# face_board.net
KiCad netlist of a schematic drawn in Altium Designer
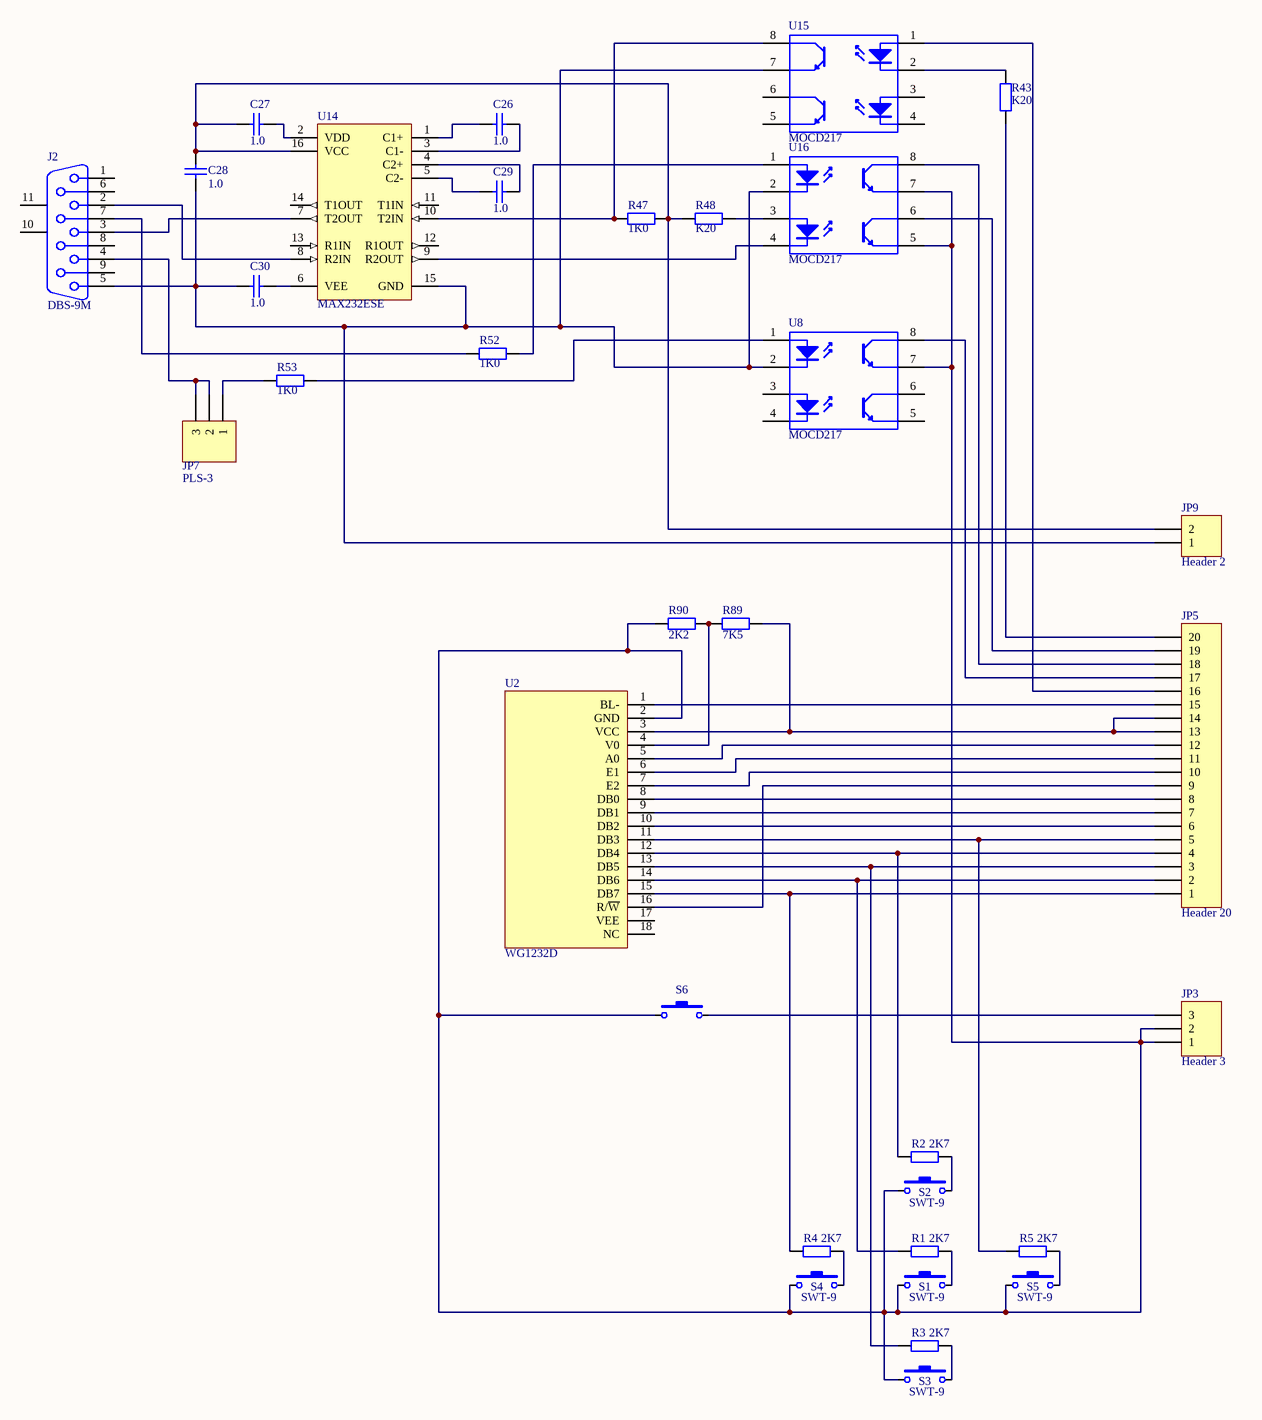
[diagram p0: face_board.SchDoc]

(export (version "E")
  (design (tool "Eeschema 10.0.6"))
  (components
    (comp (ref "C26")
      (value "1.0")
      (footprint "C3216-1206")
      (description "Capacitor (Semiconductor SIM Model)")
      (fields (field (name "MANUFACTURER") "Generic Components") (field (name "PUBLISHER") "Altium Limited"))
      (libsource (lib "Miscellaneous Devices") (part "Cap Semi"))
    )
    (comp (ref "C27")
      (value "1.0")
      (footprint "_1206")
      (description "Capacitor (Semiconductor SIM Model)")
      (fields (field (name "MANUFACTURER") "Generic Components") (field (name "PUBLISHER") "Altium Limited"))
      (libsource (lib "Miscellaneous Devices") (part "Cap Semi"))
    )
    (comp (ref "C28")
      (value "1.0")
      (footprint "C3216-1206")
      (description "Capacitor (Semiconductor SIM Model)")
      (fields (field (name "MANUFACTURER") "Generic Components") (field (name "PUBLISHER") "Altium Limited"))
      (libsource (lib "") (part "Cap Semi_1"))
    )
    (comp (ref "C29")
      (value "1.0")
      (footprint "C3216-1206")
      (description "Capacitor (Semiconductor SIM Model)")
      (fields (field (name "MANUFACTURER") "Generic Components") (field (name "PUBLISHER") "Altium Limited"))
      (libsource (lib "Miscellaneous Devices") (part "Cap Semi"))
    )
    (comp (ref "C30")
      (value "1.0")
      (footprint "C3216-1206")
      (description "Capacitor (Semiconductor SIM Model)")
      (fields (field (name "MANUFACTURER") "Generic Components") (field (name "PUBLISHER") "Altium Limited"))
      (libsource (lib "Miscellaneous Devices") (part "Cap Semi"))
    )
    (comp (ref "J2")
      (value "DBS-9M")
      (footprint "DSUB_N9")
      (description "Receptacle Assembly, 9 Position, Right Angle")
      (fields (field (name "MANUFACTURER") "Generic Components") (field (name "PUBLISHER") "Altium Limited"))
      (libsource (lib "Miscellaneous Connectors") (part "D Connector 9"))
    )
    (comp (ref "JP3")
      (value "Header 3")
      (footprint "HDR1X3")
      (description "Header, 3-Pin")
      (fields (field (name "MANUFACTURER") "Generic Components") (field (name "PUBLISHER") "Altium Limited"))
      (libsource (lib "") (part "Header 3_1"))
    )
    (comp (ref "JP5")
      (value "Header 20")
      (footprint "HDR1X20")
      (description "Header, 20-Pin")
      (fields (field (name "MANUFACTURER") "Generic Components") (field (name "PUBLISHER") "Altium Limited"))
      (libsource (lib "Miscellaneous Connectors") (part "Header 20"))
    )
    (comp (ref "JP7")
      (value "PLS-3")
      (footprint "HDR1X3")
      (description "Header, 3-Pin")
      (fields (field (name "MANUFACTURER") "Generic Components") (field (name "PUBLISHER") "Altium Limited"))
      (libsource (lib "Miscellaneous Connectors") (part "Header 3"))
    )
    (comp (ref "JP9")
      (value "Header 2")
      (footprint "HDR1X2")
      (description "Header, 2-Pin")
      (fields (field (name "MANUFACTURER") "Generic Components") (field (name "PUBLISHER") "Altium Limited"))
      (libsource (lib "Miscellaneous Connectors") (part "Header 2"))
    )
    (comp (ref "R1")
      (value "2K7")
      (footprint "_1206")
      (description "Resistor")
      (fields (field (name "MANUFACTURER") "Generic Components") (field (name "PUBLISHER") "Altium Limited"))
      (libsource (lib "Miscellaneous Devices") (part "Res2"))
    )
    (comp (ref "R2")
      (value "2K7")
      (footprint "_1206")
      (description "Resistor")
      (fields (field (name "MANUFACTURER") "Generic Components") (field (name "PUBLISHER") "Altium Limited"))
      (libsource (lib "Miscellaneous Devices") (part "Res2"))
    )
    (comp (ref "R3")
      (value "2K7")
      (footprint "_1206")
      (description "Resistor")
      (fields (field (name "MANUFACTURER") "Generic Components") (field (name "PUBLISHER") "Altium Limited"))
      (libsource (lib "Miscellaneous Devices") (part "Res2"))
    )
    (comp (ref "R4")
      (value "2K7")
      (footprint "_1206")
      (description "Resistor")
      (fields (field (name "MANUFACTURER") "Generic Components") (field (name "PUBLISHER") "Altium Limited"))
      (libsource (lib "Miscellaneous Devices") (part "Res2"))
    )
    (comp (ref "R5")
      (value "2K7")
      (footprint "_1206")
      (description "Resistor")
      (fields (field (name "MANUFACTURER") "Generic Components") (field (name "PUBLISHER") "Altium Limited"))
      (libsource (lib "Miscellaneous Devices") (part "Res2"))
    )
    (comp (ref "R43")
      (value "K20")
      (footprint "_1206")
      (description "Resistor")
      (fields (field (name "MANUFACTURER") "Generic Components") (field (name "PUBLISHER") "Altium Limited"))
      (libsource (lib "") (part "Res2_2"))
    )
    (comp (ref "R47")
      (value "1K0")
      (footprint "_1206")
      (description "Resistor")
      (fields (field (name "MANUFACTURER") "Generic Components") (field (name "PUBLISHER") "Altium Limited"))
      (libsource (lib "Miscellaneous Devices") (part "Res2"))
    )
    (comp (ref "R48")
      (value "K20")
      (footprint "_1206")
      (description "Resistor")
      (fields (field (name "MANUFACTURER") "Generic Components") (field (name "PUBLISHER") "Altium Limited"))
      (libsource (lib "Miscellaneous Devices") (part "Res2"))
    )
    (comp (ref "R52")
      (value "1K0")
      (footprint "_1206")
      (description "Resistor")
      (fields (field (name "MANUFACTURER") "Generic Components") (field (name "PUBLISHER") "Altium Limited"))
      (libsource (lib "Miscellaneous Devices") (part "Res2"))
    )
    (comp (ref "R53")
      (value "1K0")
      (footprint "_1206")
      (description "Resistor")
      (fields (field (name "MANUFACTURER") "Generic Components") (field (name "PUBLISHER") "Altium Limited"))
      (libsource (lib "Miscellaneous Devices") (part "Res2"))
    )
    (comp (ref "R89")
      (value "7K5")
      (footprint "_1206")
      (description "Resistor")
      (fields (field (name "MANUFACTURER") "Generic Components") (field (name "PUBLISHER") "Altium Limited"))
      (libsource (lib "") (part "Res2_1"))
    )
    (comp (ref "R90")
      (value "2K2")
      (footprint "_1206")
      (description "Resistor")
      (fields (field (name "MANUFACTURER") "Generic Components") (field (name "PUBLISHER") "Altium Limited"))
      (libsource (lib "") (part "Res2_1"))
    )
    (comp (ref "S1")
      (value "SWT-9")
      (footprint "SWT-9")
      (description "Switch")
      (fields (field (name "MANUFACTURER") "Generic Components") (field (name "PUBLISHER") "Altium Limited"))
      (libsource (lib "PAL") (part "SWT-9"))
    )
    (comp (ref "S2")
      (value "SWT-9")
      (footprint "SWT-9")
      (description "Switch")
      (fields (field (name "MANUFACTURER") "Generic Components") (field (name "PUBLISHER") "Altium Limited"))
      (libsource (lib "PAL") (part "SWT-9"))
    )
    (comp (ref "S3")
      (value "SWT-9")
      (footprint "SWT-9")
      (description "Switch")
      (fields (field (name "MANUFACTURER") "Generic Components") (field (name "PUBLISHER") "Altium Limited"))
      (libsource (lib "PAL") (part "SWT-9"))
    )
    (comp (ref "S4")
      (value "SWT-9")
      (footprint "SWT-9")
      (description "Switch")
      (fields (field (name "MANUFACTURER") "Generic Components") (field (name "PUBLISHER") "Altium Limited"))
      (libsource (lib "PAL") (part "SWT-9"))
    )
    (comp (ref "S5")
      (value "SWT-9")
      (footprint "SWT-9")
      (description "Switch")
      (fields (field (name "MANUFACTURER") "Generic Components") (field (name "PUBLISHER") "Altium Limited"))
      (libsource (lib "PAL") (part "SWT-9"))
    )
    (comp (ref "S6")
      (value "SWT-6")
      (footprint "SWT-6")
      (description "Button")
      (fields (field (name "MANUFACTURER") "Generic Components") (field (name "PUBLISHER") "Altium Limited"))
      (libsource (lib "PAL") (part "SWT-9"))
    )
    (comp (ref "U2") (value "WG1232D") (footprint "WG1232D") (libsource (lib "PAL") (part "WG1232D")))
    (comp (ref "U8") (value "MOCD217") (footprint "SO-G8") (libsource (lib "PAL") (part "MOCD217")))
    (comp (ref "U14")
      (value "MAX232ESE")
      (footprint "SO-G16")
      (description "+5V Powered, Multi-Channel RS-232 Driver/Receiver")
      (fields (field (name "MANUFACTURER") "Maxim") (field (name "PUBLISHER") "Altium Limited"))
      (libsource (lib "Maxim Communication Transceiver") (part "MAX232ESE"))
    )
    (comp (ref "U15") (value "MOCD217") (footprint "SO-G8") (libsource (lib "PAL") (part "MOCD217")))
    (comp (ref "U16") (value "MOCD217") (footprint "SO-G8") (libsource (lib "PAL") (part "MOCD217")))
  )
  (nets
    (net (code "1") (name "Net-(J2-Pad4)") (class "Default")
      (node (ref "J2") (pin "4") (pinfunction "4_4") (pintype "passive"))
      (node (ref "JP7") (pin "2") (pinfunction "2_2") (pintype "passive"))
      (node (ref "JP7") (pin "3") (pinfunction "3_3") (pintype "passive"))
    )
    (net (code "2") (name "Net-(J2-Pad7)") (class "Default")
      (node (ref "J2") (pin "7") (pinfunction "7_7") (pintype "passive"))
      (node (ref "R52") (pin "2") (pinfunction "2_2") (pintype "passive"))
    )
    (net (code "3") (name "Net-(JP3-Pad3)") (class "Default")
      (node (ref "JP3") (pin "3") (pinfunction "3_3") (pintype "passive"))
      (node (ref "S6") (pin "2") (pinfunction "2_2") (pintype "passive"))
    )
    (net (code "4") (name "Net-(JP5-Pad16)") (class "Default")
      (node (ref "JP5") (pin "16") (pinfunction "16_16") (pintype "passive"))
      (node (ref "U15") (pin "1") (pinfunction "A_1") (pintype "passive"))
    )
    (net (code "5") (name "Net-(JP5-Pad17)") (class "Default")
      (node (ref "JP5") (pin "17") (pinfunction "17_17") (pintype "passive"))
      (node (ref "U8") (pin "8") (pinfunction "C_8") (pintype "passive"))
    )
    (net (code "6") (name "Net-(JP5-Pad18)") (class "Default")
      (node (ref "JP5") (pin "18") (pinfunction "18_18") (pintype "passive"))
      (node (ref "U16") (pin "8") (pinfunction "C_8") (pintype "passive"))
    )
    (net (code "7") (name "Net-(JP5-Pad19)") (class "Default")
      (node (ref "JP5") (pin "19") (pinfunction "19_19") (pintype "passive"))
      (node (ref "U16") (pin "6") (pinfunction "C_6") (pintype "passive"))
    )
    (net (code "8") (name "Net-(JP5-Pad20)") (class "Default")
      (node (ref "JP5") (pin "20") (pinfunction "20_20") (pintype "passive"))
      (node (ref "R43") (pin "1") (pinfunction "1_1") (pintype "passive"))
    )
    (net (code "9") (name "Net-(JP7-Pad1)") (class "Default")
      (node (ref "JP7") (pin "1") (pinfunction "1_1") (pintype "passive"))
      (node (ref "R53") (pin "2") (pinfunction "2_2") (pintype "passive"))
    )
    (net (code "10") (name "Net-(R1-Pad1)") (class "Default")
      (node (ref "R1") (pin "1") (pinfunction "1_1") (pintype "passive"))
      (node (ref "S1") (pin "2") (pinfunction "2_2") (pintype "passive"))
    )
    (net (code "11") (name "Net-(R2-Pad1)") (class "Default")
      (node (ref "R2") (pin "1") (pinfunction "1_1") (pintype "passive"))
      (node (ref "S2") (pin "2") (pinfunction "2_2") (pintype "passive"))
    )
    (net (code "12") (name "Net-(R3-Pad1)") (class "Default")
      (node (ref "R3") (pin "1") (pinfunction "1_1") (pintype "passive"))
      (node (ref "S3") (pin "2") (pinfunction "2_2") (pintype "passive"))
    )
    (net (code "13") (name "Net-(R4-Pad1)") (class "Default")
      (node (ref "R4") (pin "1") (pinfunction "1_1") (pintype "passive"))
      (node (ref "S4") (pin "2") (pinfunction "2_2") (pintype "passive"))
    )
    (net (code "14") (name "Net-(R5-Pad1)") (class "Default")
      (node (ref "R5") (pin "1") (pinfunction "1_1") (pintype "passive"))
      (node (ref "S5") (pin "2") (pinfunction "2_2") (pintype "passive"))
    )
    (net (code "15") (name "Net-(R43-Pad2)") (class "Default")
      (node (ref "R43") (pin "2") (pinfunction "2_2") (pintype "passive"))
      (node (ref "U15") (pin "2") (pinfunction "K_2") (pintype "passive"))
    )
    (net (code "16") (name "Net-(R48-Pad1)") (class "Default")
      (node (ref "R48") (pin "1") (pinfunction "1_1") (pintype "passive"))
      (node (ref "U16") (pin "3") (pinfunction "A_3") (pintype "passive"))
    )
    (net (code "17") (name "Net-(R52-Pad1)") (class "Default")
      (node (ref "R52") (pin "1") (pinfunction "1_1") (pintype "passive"))
      (node (ref "U16") (pin "1") (pinfunction "A_1") (pintype "passive"))
    )
    (net (code "18") (name "Net-(R53-Pad1)") (class "Default")
      (node (ref "R53") (pin "1") (pinfunction "1_1") (pintype "passive"))
      (node (ref "U8") (pin "1") (pinfunction "A_1") (pintype "passive"))
    )
    (net (code "19") (name "Net-(U2-A0)") (class "Default")
      (node (ref "JP5") (pin "12") (pinfunction "12_12") (pintype "passive"))
      (node (ref "U2") (pin "5") (pinfunction "A0_5") (pintype "passive"))
    )
    (net (code "20") (name "Net-(U2-BL-)") (class "Default")
      (node (ref "JP5") (pin "15") (pinfunction "15_15") (pintype "passive"))
      (node (ref "U2") (pin "1") (pinfunction "BL-_1") (pintype "passive"))
    )
    (net (code "21") (name "Net-(U2-DB0)") (class "Default")
      (node (ref "JP5") (pin "8") (pinfunction "8_8") (pintype "passive"))
      (node (ref "U2") (pin "8") (pinfunction "DB0_8") (pintype "passive"))
    )
    (net (code "22") (name "Net-(U2-DB1)") (class "Default")
      (node (ref "JP5") (pin "7") (pinfunction "7_7") (pintype "passive"))
      (node (ref "U2") (pin "9") (pinfunction "DB1_9") (pintype "passive"))
    )
    (net (code "23") (name "Net-(U2-DB2)") (class "Default")
      (node (ref "JP5") (pin "6") (pinfunction "6_6") (pintype "passive"))
      (node (ref "U2") (pin "10") (pinfunction "DB2_10") (pintype "passive"))
    )
    (net (code "24") (name "Net-(U2-DB3)") (class "Default")
      (node (ref "JP5") (pin "5") (pinfunction "5_5") (pintype "passive"))
      (node (ref "R5") (pin "2") (pinfunction "2_2") (pintype "passive"))
      (node (ref "U2") (pin "11") (pinfunction "DB3_11") (pintype "passive"))
    )
    (net (code "25") (name "Net-(U2-DB4)") (class "Default")
      (node (ref "JP5") (pin "4") (pinfunction "4_4") (pintype "passive"))
      (node (ref "R2") (pin "2") (pinfunction "2_2") (pintype "passive"))
      (node (ref "U2") (pin "12") (pinfunction "DB4_12") (pintype "passive"))
    )
    (net (code "26") (name "Net-(U2-DB5)") (class "Default")
      (node (ref "JP5") (pin "3") (pinfunction "3_3") (pintype "passive"))
      (node (ref "R3") (pin "2") (pinfunction "2_2") (pintype "passive"))
      (node (ref "U2") (pin "13") (pinfunction "DB5_13") (pintype "passive"))
    )
    (net (code "27") (name "Net-(U2-DB6)") (class "Default")
      (node (ref "JP5") (pin "2") (pinfunction "2_2") (pintype "passive"))
      (node (ref "R1") (pin "2") (pinfunction "2_2") (pintype "passive"))
      (node (ref "U2") (pin "14") (pinfunction "DB6_14") (pintype "passive"))
    )
    (net (code "28") (name "Net-(U2-DB7)") (class "Default")
      (node (ref "JP5") (pin "1") (pinfunction "1_1") (pintype "passive"))
      (node (ref "R4") (pin "2") (pinfunction "2_2") (pintype "passive"))
      (node (ref "U2") (pin "15") (pinfunction "DB7_15") (pintype "passive"))
    )
    (net (code "29") (name "Net-(U2-E1)") (class "Default")
      (node (ref "JP5") (pin "11") (pinfunction "11_11") (pintype "passive"))
      (node (ref "U2") (pin "6") (pinfunction "E1_6") (pintype "passive"))
    )
    (net (code "30") (name "Net-(U2-E2)") (class "Default")
      (node (ref "JP5") (pin "10") (pinfunction "10_10") (pintype "passive"))
      (node (ref "U2") (pin "7") (pinfunction "E2_7") (pintype "passive"))
    )
    (net (code "31") (name "Net-(U2-GND)") (class "Default")
      (node (ref "JP3") (pin "1") (pinfunction "1_1") (pintype "passive"))
      (node (ref "JP3") (pin "2") (pinfunction "2_2") (pintype "passive"))
      (node (ref "R90") (pin "2") (pinfunction "2_2") (pintype "passive"))
      (node (ref "S1") (pin "1") (pinfunction "1_1") (pintype "passive"))
      (node (ref "S2") (pin "1") (pinfunction "1_1") (pintype "passive"))
      (node (ref "S3") (pin "1") (pinfunction "1_1") (pintype "passive"))
      (node (ref "S4") (pin "1") (pinfunction "1_1") (pintype "passive"))
      (node (ref "S5") (pin "1") (pinfunction "1_1") (pintype "passive"))
      (node (ref "S6") (pin "1") (pinfunction "1_1") (pintype "passive"))
      (node (ref "U16") (pin "5") (pinfunction "E_5") (pintype "passive"))
      (node (ref "U16") (pin "7") (pinfunction "E_7") (pintype "passive"))
      (node (ref "U2") (pin "2") (pinfunction "GND_2") (pintype "passive"))
      (node (ref "U8") (pin "7") (pinfunction "E_7") (pintype "passive"))
    )
    (net (code "32") (name "Net-(U2-R{slash}~{W})") (class "Default")
      (node (ref "JP5") (pin "9") (pinfunction "9_9") (pintype "passive"))
      (node (ref "U2") (pin "16") (pinfunction "R/~{W}_16") (pintype "passive"))
    )
    (net (code "33") (name "Net-(U2-V0)") (class "Default")
      (node (ref "R89") (pin "2") (pinfunction "2_2") (pintype "passive"))
      (node (ref "R90") (pin "1") (pinfunction "1_1") (pintype "passive"))
      (node (ref "U2") (pin "4") (pinfunction "V0_4") (pintype "passive"))
    )
    (net (code "34") (name "Net-(U2-VCC)") (class "Default")
      (node (ref "JP5") (pin "13") (pinfunction "13_13") (pintype "passive"))
      (node (ref "JP5") (pin "14") (pinfunction "14_14") (pintype "passive"))
      (node (ref "R89") (pin "1") (pinfunction "1_1") (pintype "passive"))
      (node (ref "U2") (pin "3") (pinfunction "VCC_3") (pintype "passive"))
    )
    (net (code "35") (name "Net-(U14-C1+)") (class "Default")
      (node (ref "C26") (pin "2") (pinfunction "2_2") (pintype "passive"))
      (node (ref "U14") (pin "1") (pinfunction "C1+_1") (pintype "passive"))
    )
    (net (code "36") (name "Net-(U14-C1-)") (class "Default")
      (node (ref "C26") (pin "1") (pinfunction "1_1") (pintype "passive"))
      (node (ref "U14") (pin "3") (pinfunction "C1-_3") (pintype "passive"))
    )
    (net (code "37") (name "Net-(U14-C2+)") (class "Default")
      (node (ref "C29") (pin "1") (pinfunction "1_1") (pintype "passive"))
      (node (ref "U14") (pin "4") (pinfunction "C2+_4") (pintype "passive"))
    )
    (net (code "38") (name "Net-(U14-C2-)") (class "Default")
      (node (ref "C29") (pin "2") (pinfunction "2_2") (pintype "passive"))
      (node (ref "U14") (pin "5") (pinfunction "C2-_5") (pintype "passive"))
    )
    (net (code "39") (name "Net-(U14-GND)") (class "Default")
      (node (ref "C28") (pin "2") (pinfunction "2_2") (pintype "passive"))
      (node (ref "C30") (pin "2") (pinfunction "2_2") (pintype "passive"))
      (node (ref "J2") (pin "5") (pinfunction "5_5") (pintype "passive"))
      (node (ref "JP9") (pin "1") (pinfunction "1_1") (pintype "passive"))
      (node (ref "U14") (pin "15") (pinfunction "GND_15") (pintype "power_in"))
      (node (ref "U15") (pin "7") (pinfunction "E_7") (pintype "passive"))
      (node (ref "U16") (pin "2") (pinfunction "K_2") (pintype "passive"))
      (node (ref "U8") (pin "2") (pinfunction "K_2") (pintype "passive"))
    )
    (net (code "40") (name "Net-(U14-R2IN)") (class "Default")
      (node (ref "J2") (pin "2") (pinfunction "2_2") (pintype "passive"))
      (node (ref "U14") (pin "8") (pinfunction "R2IN_8") (pintype "input"))
    )
    (net (code "41") (name "Net-(U14-R2OUT)") (class "Default")
      (node (ref "U14") (pin "9") (pinfunction "R2OUT_9") (pintype "output"))
      (node (ref "U16") (pin "4") (pinfunction "K_4") (pintype "passive"))
    )
    (net (code "42") (name "Net-(U14-T2IN)") (class "Default")
      (node (ref "R47") (pin "2") (pinfunction "2_2") (pintype "passive"))
      (node (ref "U14") (pin "10") (pinfunction "T2IN_10") (pintype "input"))
      (node (ref "U15") (pin "8") (pinfunction "C_8") (pintype "passive"))
    )
    (net (code "43") (name "Net-(U14-T2OUT)") (class "Default")
      (node (ref "J2") (pin "3") (pinfunction "3_3") (pintype "passive"))
      (node (ref "U14") (pin "7") (pinfunction "T2OUT_7") (pintype "output"))
    )
    (net (code "44") (name "Net-(U14-VCC)") (class "Default")
      (node (ref "C27") (pin "2") (pinfunction "2_2") (pintype "passive"))
      (node (ref "C28") (pin "1") (pinfunction "1_1") (pintype "passive"))
      (node (ref "JP9") (pin "2") (pinfunction "2_2") (pintype "passive"))
      (node (ref "R47") (pin "1") (pinfunction "1_1") (pintype "passive"))
      (node (ref "R48") (pin "2") (pinfunction "2_2") (pintype "passive"))
      (node (ref "U14") (pin "16") (pinfunction "VCC_16") (pintype "power_in"))
    )
    (net (code "45") (name "Net-(U14-VDD)") (class "Default")
      (node (ref "C27") (pin "1") (pinfunction "1_1") (pintype "passive"))
      (node (ref "U14") (pin "2") (pinfunction "VDD_2") (pintype "power_in"))
    )
    (net (code "46") (name "Net-(U14-VEE)") (class "Default")
      (node (ref "C30") (pin "1") (pinfunction "1_1") (pintype "passive"))
      (node (ref "U14") (pin "6") (pinfunction "VEE_6") (pintype "power_in"))
    )
    (net (code "47") (name "unconnected-(J2-MH1-Pad10)") (class "Default")
      (node (ref "J2") (pin "10") (pinfunction "MH1_10") (pintype "passive"))
    )
    (net (code "48") (name "unconnected-(J2-MH2-Pad11)") (class "Default")
      (node (ref "J2") (pin "11") (pinfunction "MH2_11") (pintype "passive"))
    )
    (net (code "49") (name "unconnected-(J2-Pad1)") (class "Default")
      (node (ref "J2") (pin "1") (pinfunction "1_1") (pintype "passive"))
    )
    (net (code "50") (name "unconnected-(J2-Pad6)") (class "Default")
      (node (ref "J2") (pin "6") (pinfunction "6_6") (pintype "passive"))
    )
    (net (code "51") (name "unconnected-(J2-Pad8)") (class "Default")
      (node (ref "J2") (pin "8") (pinfunction "8_8") (pintype "passive"))
    )
    (net (code "52") (name "unconnected-(J2-Pad9)") (class "Default")
      (node (ref "J2") (pin "9") (pinfunction "9_9") (pintype "passive"))
    )
    (net (code "53") (name "unconnected-(U2-NC-Pad18)") (class "Default")
      (node (ref "U2") (pin "18") (pinfunction "NC_18") (pintype "passive"))
    )
    (net (code "54") (name "unconnected-(U2-VEE-Pad17)") (class "Default")
      (node (ref "U2") (pin "17") (pinfunction "VEE_17") (pintype "passive"))
    )
    (net (code "55") (name "unconnected-(U8-A-Pad3)") (class "Default")
      (node (ref "U8") (pin "3") (pinfunction "A_3") (pintype "passive"))
    )
    (net (code "56") (name "unconnected-(U8-C-Pad6)") (class "Default")
      (node (ref "U8") (pin "6") (pinfunction "C_6") (pintype "passive"))
    )
    (net (code "57") (name "unconnected-(U8-E-Pad5)") (class "Default")
      (node (ref "U8") (pin "5") (pinfunction "E_5") (pintype "passive"))
    )
    (net (code "58") (name "unconnected-(U8-K-Pad4)") (class "Default")
      (node (ref "U8") (pin "4") (pinfunction "K_4") (pintype "passive"))
    )
    (net (code "59") (name "unconnected-(U14-R1IN-Pad13)") (class "Default")
      (node (ref "U14") (pin "13") (pinfunction "R1IN_13") (pintype "input"))
    )
    (net (code "60") (name "unconnected-(U14-R1OUT-Pad12)") (class "Default")
      (node (ref "U14") (pin "12") (pinfunction "R1OUT_12") (pintype "output"))
    )
    (net (code "61") (name "unconnected-(U14-T1IN-Pad11)") (class "Default")
      (node (ref "U14") (pin "11") (pinfunction "T1IN_11") (pintype "input"))
    )
    (net (code "62") (name "unconnected-(U14-T1OUT-Pad14)") (class "Default")
      (node (ref "U14") (pin "14") (pinfunction "T1OUT_14") (pintype "output"))
    )
    (net (code "63") (name "unconnected-(U15-A-Pad3)") (class "Default")
      (node (ref "U15") (pin "3") (pinfunction "A_3") (pintype "passive"))
    )
    (net (code "64") (name "unconnected-(U15-C-Pad6)") (class "Default")
      (node (ref "U15") (pin "6") (pinfunction "C_6") (pintype "passive"))
    )
    (net (code "65") (name "unconnected-(U15-E-Pad5)") (class "Default")
      (node (ref "U15") (pin "5") (pinfunction "E_5") (pintype "passive"))
    )
    (net (code "66") (name "unconnected-(U15-K-Pad4)") (class "Default")
      (node (ref "U15") (pin "4") (pinfunction "K_4") (pintype "passive"))
    )
  )
)
